# charging_board.net
KiCad netlist of a schematic drawn in Altium Designer
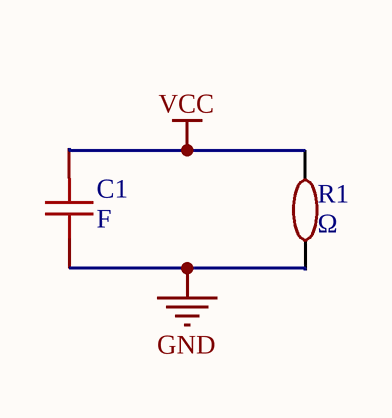
[diagram p0: charging_board.SchDoc]

(export (version "E")
  (design (tool "Eeschema 10.0.6"))
  (components
    (comp (ref "C1")
      (value "F")
      (footprint "0603")
      (description "0603封装电容")
      (libsource (lib "XJTLU_Torpedo") (part "C0603"))
    )
    (comp (ref "R1")
      (value "Ω")
      (footprint "0603")
      (description "0603封装电阻")
      (libsource (lib "XJTLU_Torpedo") (part "R0603"))
    )
  )
  (nets
    (net (code "1") (name "GND") (class "Default")
      (node (ref "C1") (pin "1") (pinfunction "1_1") (pintype "passive"))
      (node (ref "R1") (pin "1") (pinfunction "1_1") (pintype "passive"))
    )
    (net (code "2") (name "VCC") (class "Default")
      (node (ref "C1") (pin "2") (pinfunction "2_2") (pintype "passive"))
      (node (ref "R1") (pin "2") (pinfunction "2_2") (pintype "passive"))
    )
  )
)
